# TempSensor.net
KiCad netlist of a schematic drawn in EAGLE
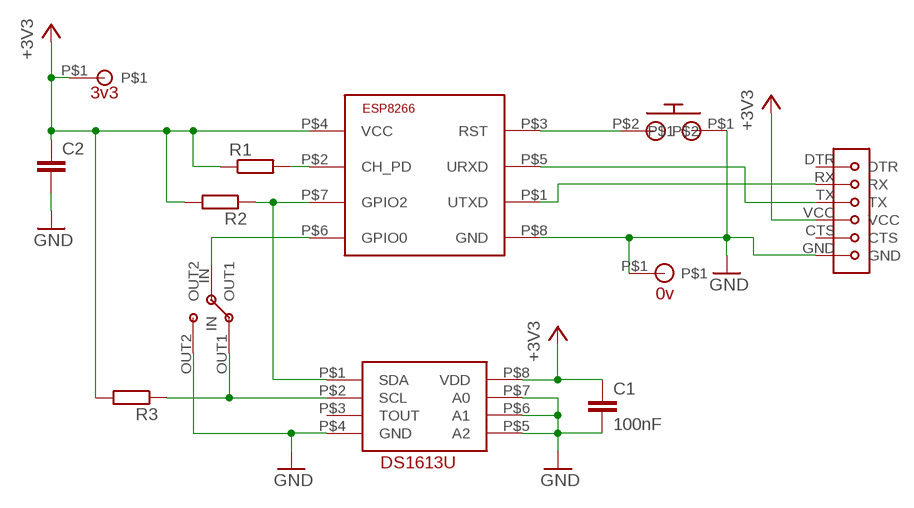
[diagram p0: schematic, sheet 1]

(export (version "E")
  (design (tool "Eeschema 10.0.6"))
  (components
    (comp (ref "C1")
      (value "100nF")
      (footprint "eagle-import:C025-025X050")
      (libsource (lib "eagle-import") (part "C-EU025-025X050"))
    )
    (comp (ref "C2")
      (value "C-EU025-025X050")
      (footprint "eagle-import:C025-025X050")
      (libsource (lib "eagle-import") (part "C-EU025-025X050"))
    )
    (comp (ref "R1")
      (value "R-EU_0207/10")
      (footprint "eagle-import:0207_10")
      (libsource (lib "eagle-import") (part "R-EU_0207/10"))
    )
    (comp (ref "R2")
      (value "R-EU_0207/10")
      (footprint "eagle-import:0207_10")
      (libsource (lib "eagle-import") (part "R-EU_0207/10"))
    )
    (comp (ref "R3")
      (value "R-EU_0207/10")
      (footprint "eagle-import:0207_10")
      (libsource (lib "eagle-import") (part "R-EU_0207/10"))
    )
    (comp (ref "U$1")
      (value "ESP8266-01")
      (footprint "eagle-import:ESP-01")
      (libsource (lib "eagle-import") (part "ESP8266-01"))
    )
    (comp (ref "U$2")
      (value "TACT-SWITCH")
      (footprint "eagle-import:TACT-SWITCH")
      (libsource (lib "eagle-import") (part "TACT-SWITCH"))
    )
    (comp (ref "U$3")
      (value "DS1631U-BREAKOUT")
      (footprint "eagle-import:DS1631U-BREAKOUT")
      (libsource (lib "eagle-import") (part "DS1631U-BREAKOUT"))
    )
    (comp (ref "U$4")
      (value "SPDT-SWITCH-1")
      (footprint "eagle-import:SPDT-SWITCH-1")
      (libsource (lib "eagle-import") (part "SPDT-SWITCH-1"))
    )
    (comp (ref "U$5")
      (value "FT232RL-ADAPTER")
      (footprint "eagle-import:FT232RL-ADAPTER")
      (libsource (lib "eagle-import") (part "FT232RL-ADAPTER"))
    )
    (comp (ref "U$6")
      (value "3V3")
      (footprint "eagle-import:3V3")
      (libsource (lib "eagle-import") (part "3V3"))
    )
    (comp (ref "U$7") (value "0V") (footprint "eagle-import:0V") (libsource (lib "eagle-import") (part "0V")))
  )
  (nets
    (net (code "1") (name "+3V3") (class "Default")
      (node (ref "C1") (pin "1") (pinfunction "1_1") (pintype "passive"))
      (node (ref "C2") (pin "1") (pinfunction "1_1") (pintype "passive"))
      (node (ref "R1") (pin "1") (pinfunction "1_1") (pintype "passive"))
      (node (ref "R2") (pin "2") (pinfunction "2_2") (pintype "passive"))
      (node (ref "R3") (pin "2") (pinfunction "2_2") (pintype "passive"))
      (node (ref "U$1") (pin "P$4") (pinfunction "VCC_P$4") (pintype "bidirectional"))
      (node (ref "U$3") (pin "P$8") (pinfunction "VDD_P$8") (pintype "bidirectional"))
      (node (ref "U$5") (pin "VCC") (pinfunction "VCC_VCC") (pintype "bidirectional"))
      (node (ref "U$6") (pin "P$1") (pinfunction "P$1_P$1") (pintype "bidirectional"))
    )
    (net (code "2") (name "GND") (class "Default")
      (node (ref "C1") (pin "2") (pinfunction "2_2") (pintype "passive"))
      (node (ref "C2") (pin "2") (pinfunction "2_2") (pintype "passive"))
      (node (ref "U$1") (pin "P$8") (pinfunction "GND_P$8") (pintype "bidirectional"))
      (node (ref "U$2") (pin "P$1") (pinfunction "P$1_P$1") (pintype "bidirectional"))
      (node (ref "U$3") (pin "P$4") (pinfunction "GND_P$4") (pintype "bidirectional"))
      (node (ref "U$3") (pin "P$5") (pinfunction "A2_P$5") (pintype "bidirectional"))
      (node (ref "U$3") (pin "P$6") (pinfunction "A1_P$6") (pintype "bidirectional"))
      (node (ref "U$3") (pin "P$7") (pinfunction "A0_P$7") (pintype "bidirectional"))
      (node (ref "U$4") (pin "OUT2") (pinfunction "OUT2_OUT2") (pintype "bidirectional"))
      (node (ref "U$5") (pin "GND") (pinfunction "GND_GND") (pintype "bidirectional"))
      (node (ref "U$7") (pin "P$1") (pinfunction "P$1_P$1") (pintype "bidirectional"))
    )
    (net (code "3") (name "Net-(U$1-CH_PD)") (class "Default")
      (node (ref "R1") (pin "2") (pinfunction "2_2") (pintype "passive"))
      (node (ref "U$1") (pin "P$2") (pinfunction "CH_PD_P$2") (pintype "bidirectional"))
    )
    (net (code "4") (name "Net-(U$1-GPIO0)") (class "Default")
      (node (ref "U$1") (pin "P$6") (pinfunction "GPIO0_P$6") (pintype "bidirectional"))
      (node (ref "U$4") (pin "IN") (pinfunction "IN_IN") (pintype "bidirectional"))
    )
    (net (code "5") (name "Net-(U$1-GPIO2)") (class "Default")
      (node (ref "R2") (pin "1") (pinfunction "1_1") (pintype "passive"))
      (node (ref "U$1") (pin "P$7") (pinfunction "GPIO2_P$7") (pintype "bidirectional"))
      (node (ref "U$3") (pin "P$1") (pinfunction "SDA_P$1") (pintype "bidirectional"))
    )
    (net (code "6") (name "Net-(U$1-RST)") (class "Default")
      (node (ref "U$1") (pin "P$3") (pinfunction "RST_P$3") (pintype "bidirectional"))
      (node (ref "U$2") (pin "P$2") (pinfunction "P$2_P$2") (pintype "bidirectional"))
    )
    (net (code "7") (name "Net-(U$1-URXD)") (class "Default")
      (node (ref "U$1") (pin "P$5") (pinfunction "URXD_P$5") (pintype "bidirectional"))
      (node (ref "U$5") (pin "TX") (pinfunction "TX_TX") (pintype "bidirectional"))
    )
    (net (code "8") (name "Net-(U$1-UTXD)") (class "Default")
      (node (ref "U$1") (pin "P$1") (pinfunction "UTXD_P$1") (pintype "bidirectional"))
      (node (ref "U$5") (pin "RX") (pinfunction "RX_RX") (pintype "bidirectional"))
    )
    (net (code "9") (name "Net-(U$3-SCL)") (class "Default")
      (node (ref "R3") (pin "1") (pinfunction "1_1") (pintype "passive"))
      (node (ref "U$3") (pin "P$2") (pinfunction "SCL_P$2") (pintype "bidirectional"))
      (node (ref "U$4") (pin "OUT1") (pinfunction "OUT1_OUT1") (pintype "bidirectional"))
    )
    (net (code "10") (name "unconnected-(U$3-TOUT-PadP$3)") (class "Default")
      (node (ref "U$3") (pin "P$3") (pinfunction "TOUT_P$3") (pintype "bidirectional"))
    )
    (net (code "11") (name "unconnected-(U$5-PadCTS)") (class "Default")
      (node (ref "U$5") (pin "CTS") (pinfunction "CTS_CTS") (pintype "bidirectional"))
    )
    (net (code "12") (name "unconnected-(U$5-PadDTR)") (class "Default")
      (node (ref "U$5") (pin "DTR") (pinfunction "DTR_DTR") (pintype "bidirectional"))
    )
  )
)
